# schematic_V3_1.net
KiCad netlist of a schematic drawn in EAGLE
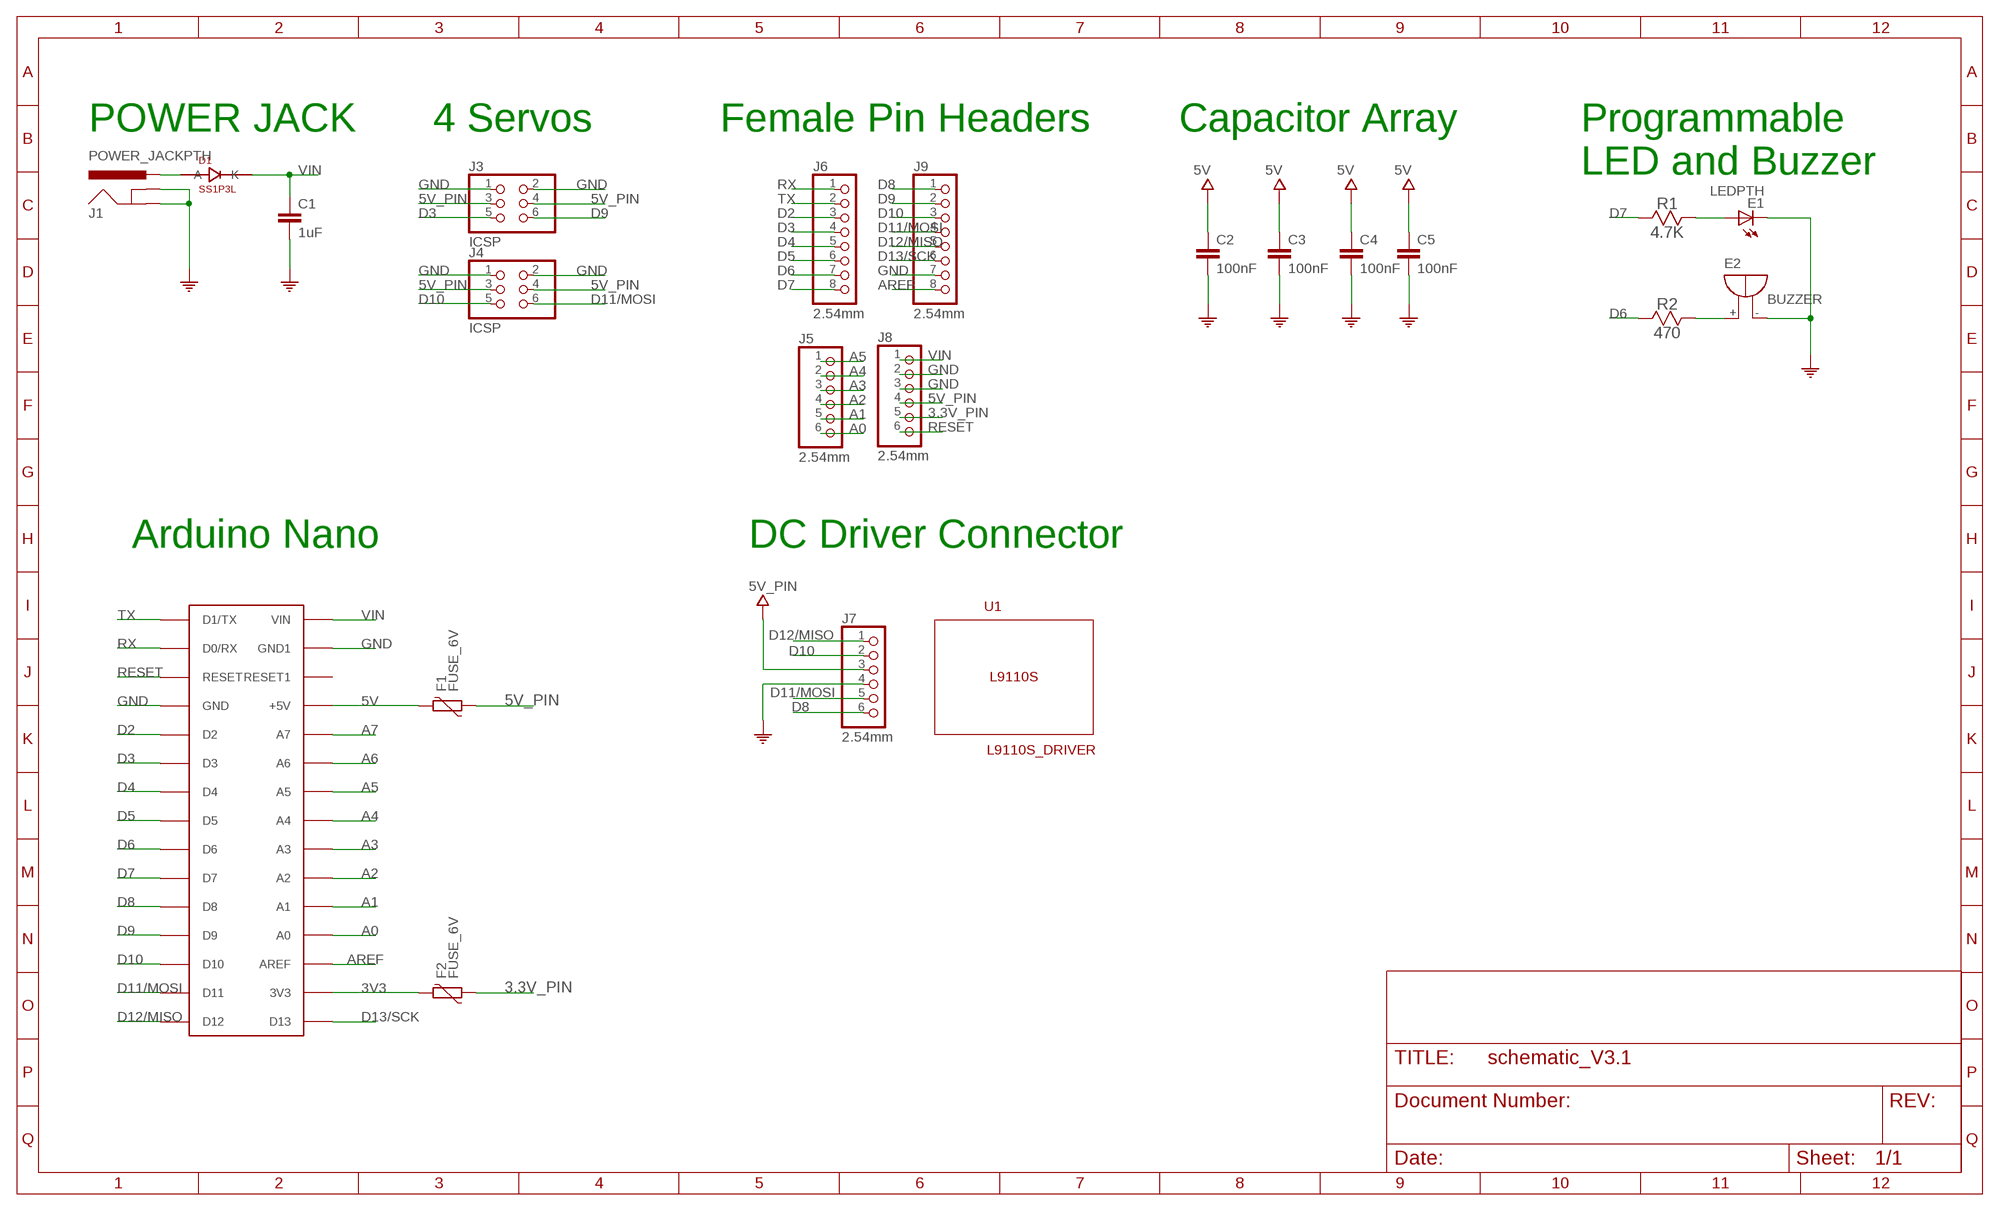
[diagram p0: schematic, sheet 1]

(export (version "E")
  (design (tool "Eeschema 10.0.6"))
  (components
    (comp (ref "C1")
      (value "1uF")
      (footprint "eagle-import:C0603-ROUND")
      (fields (field (name "PARTNO") "CC0603KRX5R8BB105"))
      (libsource (lib "eagle-import") (part "CAPACITOR_1UF_0603"))
    )
    (comp (ref "C2")
      (value "100nF")
      (footprint "eagle-import:C0603-ROUND")
      (fields (field (name "PARTNO") "CC0603ZRY5V9BB104"))
      (libsource (lib "eagle-import") (part "CAPACITOR_100NF_0603"))
    )
    (comp (ref "C3")
      (value "100nF")
      (footprint "eagle-import:C0603-ROUND")
      (fields (field (name "PARTNO") "CC0603ZRY5V9BB104"))
      (libsource (lib "eagle-import") (part "CAPACITOR_100NF_0603"))
    )
    (comp (ref "C4")
      (value "100nF")
      (footprint "eagle-import:C0603-ROUND")
      (fields (field (name "PARTNO") "CC0603ZRY5V9BB104"))
      (libsource (lib "eagle-import") (part "CAPACITOR_100NF_0603"))
    )
    (comp (ref "C5")
      (value "100nF")
      (footprint "eagle-import:C0603-ROUND")
      (fields (field (name "PARTNO") "CC0603ZRY5V9BB104"))
      (libsource (lib "eagle-import") (part "CAPACITOR_100NF_0603"))
    )
    (comp (ref "D1")
      (value "SS1P3L")
      (footprint "eagle-import:DIODI_DO220AAL")
      (fields (field (name "PARTNO") "SS1P3L-M3/84A"))
      (libsource (lib "eagle-import") (part "SCHOTTKY_DIODE"))
    )
    (comp (ref "E1")
      (value "LEDPTH")
      (footprint "eagle-import:LED5MM")
      (libsource (lib "eagle-import") (part "LEDPTH"))
    )
    (comp (ref "E2")
      (value "BUZZER")
      (footprint "eagle-import:BUZZER")
      (libsource (lib "eagle-import") (part "BUZZER"))
    )
    (comp (ref "F1")
      (value "FUSE_6V")
      (footprint "eagle-import:FUSE_0603")
      (libsource (lib "eagle-import") (part "FUSE_6V"))
    )
    (comp (ref "F2")
      (value "FUSE_6V")
      (footprint "eagle-import:FUSE_0603")
      (libsource (lib "eagle-import") (part "FUSE_6V"))
    )
    (comp (ref "J1")
      (value "POWER_JACKPTH")
      (footprint "eagle-import:POWER_JACK_PTH")
      (fields (field (name "PARTNO") "EJ508A"))
      (libsource (lib "eagle-import") (part "POWER_JACKPTH"))
    )
    (comp (ref "J2")
      (value "ARDUINONANO")
      (footprint "eagle-import:PDIP-32")
      (libsource (lib "eagle-import") (part "ARDUINONANO"))
    )
    (comp (ref "J3")
      (value "ICSP")
      (footprint "eagle-import:CONNECTOR_2X3")
      (fields (field (name "PARTNO") "M20-9980346"))
      (libsource (lib "eagle-import") (part "CONNECTOR_2X3"))
    )
    (comp (ref "J4")
      (value "ICSP")
      (footprint "eagle-import:CONNECTOR_2X3")
      (fields (field (name "PARTNO") "M20-9980346"))
      (libsource (lib "eagle-import") (part "CONNECTOR_2X3"))
    )
    (comp (ref "J5")
      (value "2.54mm")
      (footprint "eagle-import:1X06")
      (fields (field (name "PARTNO") "M20-7820646"))
      (libsource (lib "eagle-import") (part "PINHD-1X6"))
    )
    (comp (ref "J6")
      (value "2.54mm")
      (footprint "eagle-import:1X08")
      (fields (field (name "PARTNO") "PPTC081LFBN-RC"))
      (libsource (lib "eagle-import") (part "PINHD-1X8"))
    )
    (comp (ref "J7")
      (value "2.54mm")
      (footprint "eagle-import:1X06")
      (fields (field (name "PARTNO") "M20-7820646"))
      (libsource (lib "eagle-import") (part "PINHD-1X6"))
    )
    (comp (ref "J8")
      (value "2.54mm")
      (footprint "eagle-import:1X06")
      (fields (field (name "PARTNO") "M20-7820646"))
      (libsource (lib "eagle-import") (part "PINHD-1X6"))
    )
    (comp (ref "J9")
      (value "2.54mm")
      (footprint "eagle-import:1X08")
      (fields (field (name "PARTNO") "PPTC081LFBN-RC"))
      (libsource (lib "eagle-import") (part "PINHD-1X8"))
    )
    (comp (ref "R1")
      (value "4.7K")
      (footprint "eagle-import:RESISTOR_PTH")
      (libsource (lib "eagle-import") (part "RESISTOR"))
    )
    (comp (ref "R2")
      (value "470")
      (footprint "eagle-import:RESISTOR_PTH")
      (libsource (lib "eagle-import") (part "RESISTOR"))
    )
    (comp (ref "U1")
      (value "L9110S_DRIVER")
      (footprint "eagle-import:L9110S_DRIVER")
      (libsource (lib "eagle-import") (part "L9110S_DRIVER"))
    )
  )
  (nets
    (net (code "1") (name "/3.3V_PIN") (class "Default")
      (node (ref "F2") (pin "1") (pinfunction "1_1") (pintype "passive"))
      (node (ref "J8") (pin "5") (pinfunction "5_5") (pintype "passive"))
    )
    (net (code "2") (name "/3V3") (class "Default")
      (node (ref "F2") (pin "2") (pinfunction "2_2") (pintype "passive"))
      (node (ref "J2") (pin "3V3") (pinfunction "3V3_3V3") (pintype "bidirectional"))
    )
    (net (code "3") (name "/A0") (class "Default")
      (node (ref "J2") (pin "A7") (pinfunction "A0_A7") (pintype "bidirectional"))
      (node (ref "J5") (pin "6") (pinfunction "6_6") (pintype "passive"))
    )
    (net (code "4") (name "/A1") (class "Default")
      (node (ref "J2") (pin "A6") (pinfunction "A1_A6") (pintype "bidirectional"))
      (node (ref "J5") (pin "5") (pinfunction "5_5") (pintype "passive"))
    )
    (net (code "5") (name "/A2") (class "Default")
      (node (ref "J2") (pin "A5") (pinfunction "A2_A5") (pintype "bidirectional"))
      (node (ref "J5") (pin "4") (pinfunction "4_4") (pintype "passive"))
    )
    (net (code "6") (name "/A3") (class "Default")
      (node (ref "J2") (pin "A4") (pinfunction "A3_A4") (pintype "bidirectional"))
      (node (ref "J5") (pin "3") (pinfunction "3_3") (pintype "passive"))
    )
    (net (code "7") (name "/A4") (class "Default")
      (node (ref "J2") (pin "A3") (pinfunction "A4_A3") (pintype "bidirectional"))
      (node (ref "J5") (pin "2") (pinfunction "2_2") (pintype "passive"))
    )
    (net (code "8") (name "/A5") (class "Default")
      (node (ref "J2") (pin "A2") (pinfunction "A5_A2") (pintype "bidirectional"))
      (node (ref "J5") (pin "1") (pinfunction "1_1") (pintype "passive"))
    )
    (net (code "9") (name "/A6") (class "Default")
      (node (ref "J2") (pin "A1") (pinfunction "A6_A1") (pintype "bidirectional"))
    )
    (net (code "10") (name "/A7") (class "Default")
      (node (ref "J2") (pin "A0") (pinfunction "A7_A0") (pintype "bidirectional"))
    )
    (net (code "11") (name "/AREF") (class "Default")
      (node (ref "J2") (pin "AREF") (pinfunction "AREF_AREF") (pintype "bidirectional"))
      (node (ref "J9") (pin "8") (pinfunction "8_8") (pintype "passive"))
    )
    (net (code "12") (name "/D2") (class "Default")
      (node (ref "J2") (pin "D2") (pinfunction "D2_D2") (pintype "bidirectional"))
      (node (ref "J6") (pin "3") (pinfunction "3_3") (pintype "passive"))
    )
    (net (code "13") (name "/D3") (class "Default")
      (node (ref "J2") (pin "D3") (pinfunction "D3_D3") (pintype "bidirectional"))
      (node (ref "J3") (pin "5") (pinfunction "5_5") (pintype "passive"))
      (node (ref "J6") (pin "4") (pinfunction "4_4") (pintype "passive"))
    )
    (net (code "14") (name "/D4") (class "Default")
      (node (ref "J2") (pin "D4") (pinfunction "D4_D4") (pintype "bidirectional"))
      (node (ref "J6") (pin "5") (pinfunction "5_5") (pintype "passive"))
    )
    (net (code "15") (name "/D5") (class "Default")
      (node (ref "J2") (pin "D5") (pinfunction "D5_D5") (pintype "bidirectional"))
      (node (ref "J6") (pin "6") (pinfunction "6_6") (pintype "passive"))
    )
    (net (code "16") (name "/D6") (class "Default")
      (node (ref "J2") (pin "D6") (pinfunction "D6_D6") (pintype "bidirectional"))
      (node (ref "J6") (pin "7") (pinfunction "7_7") (pintype "passive"))
      (node (ref "R2") (pin "1") (pinfunction "1_1") (pintype "bidirectional"))
    )
    (net (code "17") (name "/D7") (class "Default")
      (node (ref "J2") (pin "D7") (pinfunction "D7_D7") (pintype "bidirectional"))
      (node (ref "J6") (pin "8") (pinfunction "8_8") (pintype "passive"))
      (node (ref "R1") (pin "1") (pinfunction "1_1") (pintype "bidirectional"))
    )
    (net (code "18") (name "/D8") (class "Default")
      (node (ref "J2") (pin "D8") (pinfunction "D8_D8") (pintype "bidirectional"))
      (node (ref "J7") (pin "6") (pinfunction "6_6") (pintype "passive"))
      (node (ref "J9") (pin "1") (pinfunction "1_1") (pintype "passive"))
    )
    (net (code "19") (name "/D9") (class "Default")
      (node (ref "J2") (pin "D9") (pinfunction "D9_D9") (pintype "bidirectional"))
      (node (ref "J3") (pin "6") (pinfunction "6_6") (pintype "passive"))
      (node (ref "J9") (pin "2") (pinfunction "2_2") (pintype "passive"))
    )
    (net (code "20") (name "/D10") (class "Default")
      (node (ref "J2") (pin "D10") (pinfunction "D10_D10") (pintype "bidirectional"))
      (node (ref "J4") (pin "5") (pinfunction "5_5") (pintype "passive"))
      (node (ref "J7") (pin "2") (pinfunction "2_2") (pintype "passive"))
      (node (ref "J9") (pin "3") (pinfunction "3_3") (pintype "passive"))
    )
    (net (code "21") (name "/D11{slash}MOSI") (class "Default")
      (node (ref "J2") (pin "D11") (pinfunction "D11_D11") (pintype "bidirectional"))
      (node (ref "J4") (pin "6") (pinfunction "6_6") (pintype "passive"))
      (node (ref "J7") (pin "5") (pinfunction "5_5") (pintype "passive"))
      (node (ref "J9") (pin "4") (pinfunction "4_4") (pintype "passive"))
    )
    (net (code "22") (name "/D12{slash}MISO") (class "Default")
      (node (ref "J2") (pin "D12") (pinfunction "D12_D12") (pintype "bidirectional"))
      (node (ref "J7") (pin "1") (pinfunction "1_1") (pintype "passive"))
      (node (ref "J9") (pin "5") (pinfunction "5_5") (pintype "passive"))
    )
    (net (code "23") (name "/D13{slash}SCK") (class "Default")
      (node (ref "J2") (pin "D13") (pinfunction "D13_D13") (pintype "bidirectional"))
      (node (ref "J9") (pin "6") (pinfunction "6_6") (pintype "passive"))
    )
    (net (code "24") (name "/RESET") (class "Default")
      (node (ref "J2") (pin "RESET") (pinfunction "RESET_RESET") (pintype "bidirectional"))
      (node (ref "J8") (pin "6") (pinfunction "6_6") (pintype "passive"))
    )
    (net (code "25") (name "/RX") (class "Default")
      (node (ref "J2") (pin "D0/RX") (pinfunction "D0/RX_D0/RX") (pintype "bidirectional"))
      (node (ref "J6") (pin "1") (pinfunction "1_1") (pintype "passive"))
    )
    (net (code "26") (name "/TX") (class "Default")
      (node (ref "J2") (pin "D1/TX") (pinfunction "D1/TX_D1/TX") (pintype "bidirectional"))
      (node (ref "J6") (pin "2") (pinfunction "2_2") (pintype "passive"))
    )
    (net (code "27") (name "/VIN") (class "Default")
      (node (ref "C1") (pin "1") (pinfunction "1_1") (pintype "passive"))
      (node (ref "D1") (pin "P$1") (pinfunction "K_P$1") (pintype "bidirectional"))
      (node (ref "J2") (pin "VIN") (pinfunction "VIN_VIN") (pintype "bidirectional"))
      (node (ref "J8") (pin "1") (pinfunction "1_1") (pintype "passive"))
    )
    (net (code "28") (name "5V") (class "Default")
      (node (ref "C2") (pin "1") (pinfunction "1_1") (pintype "passive"))
      (node (ref "C3") (pin "1") (pinfunction "1_1") (pintype "passive"))
      (node (ref "C4") (pin "1") (pinfunction "1_1") (pintype "passive"))
      (node (ref "C5") (pin "1") (pinfunction "1_1") (pintype "passive"))
      (node (ref "F1") (pin "2") (pinfunction "2_2") (pintype "passive"))
      (node (ref "J2") (pin "+5V") (pinfunction "+5V_+5V") (pintype "bidirectional"))
    )
    (net (code "29") (name "5V_PIN") (class "Default")
      (node (ref "F1") (pin "1") (pinfunction "1_1") (pintype "passive"))
      (node (ref "J3") (pin "3") (pinfunction "3_3") (pintype "passive"))
      (node (ref "J3") (pin "4") (pinfunction "4_4") (pintype "passive"))
      (node (ref "J4") (pin "3") (pinfunction "3_3") (pintype "passive"))
      (node (ref "J4") (pin "4") (pinfunction "4_4") (pintype "passive"))
      (node (ref "J7") (pin "3") (pinfunction "3_3") (pintype "passive"))
      (node (ref "J8") (pin "4") (pinfunction "4_4") (pintype "passive"))
    )
    (net (code "30") (name "GND") (class "Default")
      (node (ref "C1") (pin "2") (pinfunction "2_2") (pintype "passive"))
      (node (ref "C2") (pin "2") (pinfunction "2_2") (pintype "passive"))
      (node (ref "C3") (pin "2") (pinfunction "2_2") (pintype "passive"))
      (node (ref "C4") (pin "2") (pinfunction "2_2") (pintype "passive"))
      (node (ref "C5") (pin "2") (pinfunction "2_2") (pintype "passive"))
      (node (ref "E1") (pin "K") (pinfunction "C_K") (pintype "passive"))
      (node (ref "E2") (pin "-") (pinfunction "-_-") (pintype "passive"))
      (node (ref "J1") (pin "GND") (pinfunction "GND_GND") (pintype "bidirectional"))
      (node (ref "J1") (pin "GNDBREAK") (pinfunction "GNDBREAK_GNDBREAK") (pintype "bidirectional"))
      (node (ref "J2") (pin "GND") (pinfunction "GND_GND") (pintype "bidirectional"))
      (node (ref "J2") (pin "GND1") (pinfunction "GND1_GND1") (pintype "bidirectional"))
      (node (ref "J3") (pin "1") (pinfunction "1_1") (pintype "passive"))
      (node (ref "J3") (pin "2") (pinfunction "2_2") (pintype "passive"))
      (node (ref "J4") (pin "1") (pinfunction "1_1") (pintype "passive"))
      (node (ref "J4") (pin "2") (pinfunction "2_2") (pintype "passive"))
      (node (ref "J7") (pin "4") (pinfunction "4_4") (pintype "passive"))
      (node (ref "J8") (pin "2") (pinfunction "2_2") (pintype "passive"))
      (node (ref "J8") (pin "3") (pinfunction "3_3") (pintype "passive"))
      (node (ref "J9") (pin "7") (pinfunction "7_7") (pintype "passive"))
    )
    (net (code "31") (name "Net-(D1-A)") (class "Default")
      (node (ref "D1") (pin "P$2") (pinfunction "A_P$2") (pintype "bidirectional"))
      (node (ref "J1") (pin "PWR") (pinfunction "PWR_PWR") (pintype "bidirectional"))
    )
    (net (code "32") (name "Net-(E1-PadA)") (class "Default")
      (node (ref "E1") (pin "A") (pinfunction "A_A") (pintype "passive"))
      (node (ref "R1") (pin "2") (pinfunction "2_2") (pintype "bidirectional"))
    )
    (net (code "33") (name "Net-(E2-Pad+)") (class "Default")
      (node (ref "E2") (pin "+") (pinfunction "+_+") (pintype "passive"))
      (node (ref "R2") (pin "2") (pinfunction "2_2") (pintype "bidirectional"))
    )
    (net (code "34") (name "unconnected-(J2-PadRESET1)") (class "Default")
      (node (ref "J2") (pin "RESET1") (pinfunction "RESET1_RESET1") (pintype "bidirectional"))
    )
  )
)
